# SH7_-_CAN.net
KiCad netlist of a schematic drawn in Altium Designer
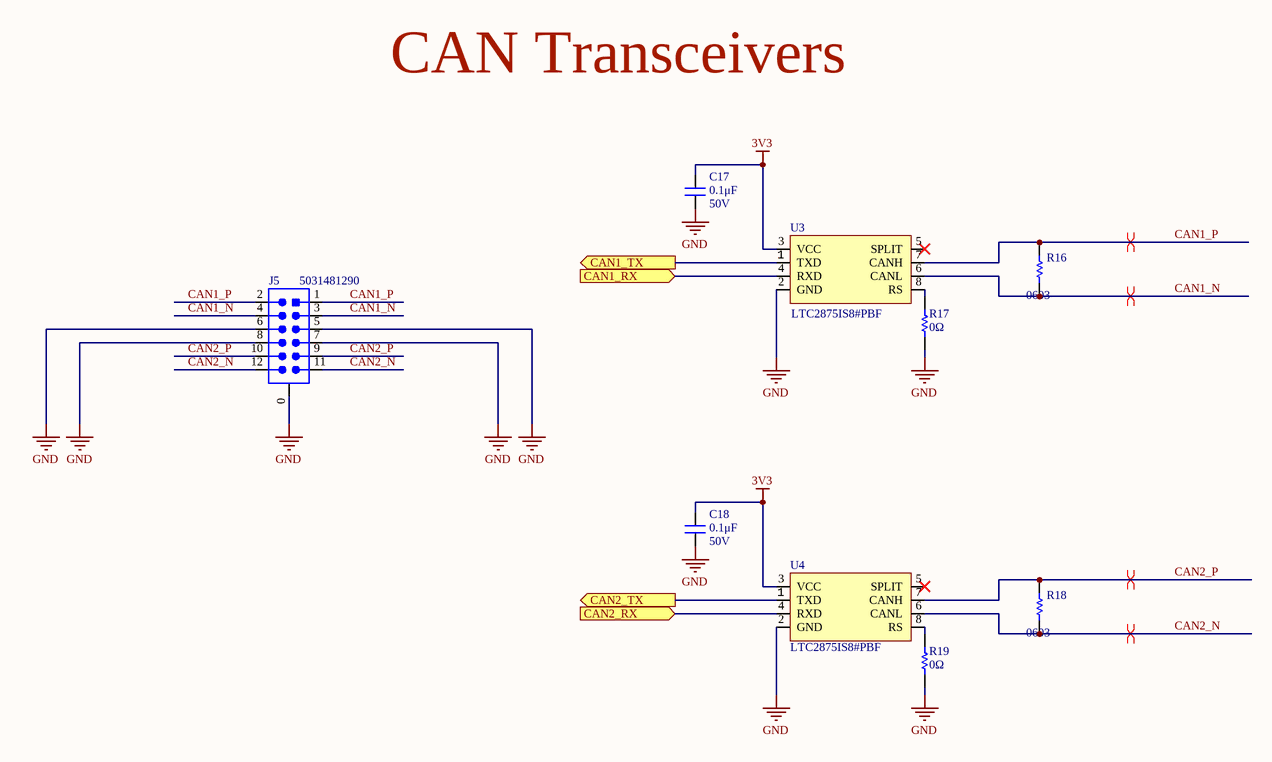
[diagram p0: SH7 - CAN.SchDoc]

(export (version "E")
  (design (tool "Eeschema 10.0.6"))
  (components
    (comp (ref "C17")
      (value "0.1μF")
      (footprint "CAP0603")
      (description "CAP CER 0.1UF 50V X7R 0603")
      (fields (field (name "VOLTAGE RATING") "50V") (field (name "Comment") "CAP_0.1uF_50V_0603"))
      (libsource (lib "UWRT_Schematic_Library_2020") (part "CAP_0.1uF_50V_0603"))
    )
    (comp (ref "C18")
      (value "0.1μF")
      (footprint "CAP0603")
      (description "CAP CER 0.1UF 50V X7R 0603")
      (fields (field (name "VOLTAGE RATING") "50V") (field (name "Comment") "CAP_0.1uF_50V_0603"))
      (libsource (lib "UWRT_Schematic_Library_2020") (part "CAP_0.1uF_50V_0603"))
    )
    (comp (ref "J5")
      (value "CON_6x2M_SM_RA")
      (footprint "MOLEX-5031481290")
      (description "CONN HEADER SMD RIGHT ANGLE 1.5MM PITCH")
      (fields (field (name "MANUFACTURER PART NUMBER 1") "5031481290"))
      (libsource (lib "UWRT_Schematic_Library_2020") (part "CON_6x2M_SM_RA"))
    )
    (comp (ref "R16")
      (value "RES_120Ω_0603_5%_HP")
      (footprint "RESC0603")
      (description "RES 120 OHM 5% 1/4W 0603")
      (fields (field (name "PACKAGE/FOOTPRINT") "0603"))
      (libsource (lib "UWRT_Schematic_Library_2020") (part "RES_120Ω_0603_5%_HP"))
    )
    (comp (ref "R17")
      (value "0Ω")
      (footprint "RESC0603")
      (description "RES 0 OHM JUMPER 1/10W 0603")
      (fields (field (name "Comment") "RES_0Ω_0603"))
      (libsource (lib "UWRT_Schematic_Library_2020") (part "RES_0Ω_0603"))
    )
    (comp (ref "R18")
      (value "RES_120Ω_0603_5%_HP")
      (footprint "RESC0603")
      (description "RES 120 OHM 5% 1/4W 0603")
      (fields (field (name "PACKAGE/FOOTPRINT") "0603"))
      (libsource (lib "UWRT_Schematic_Library_2020") (part "RES_120Ω_0603_5%_HP"))
    )
    (comp (ref "R19")
      (value "0Ω")
      (footprint "RESC0603")
      (description "RES 0 OHM JUMPER 1/10W 0603")
      (fields (field (name "Comment") "RES_0Ω_0603"))
      (libsource (lib "UWRT_Schematic_Library_2020") (part "RES_0Ω_0603"))
    )
    (comp (ref "U3")
      (value "LTC2875")
      (footprint "LT-S8_N")
      (description "IC TXRX CAN 4MBPS 8SO")
      (fields
        (field (name "MANUFACTURER PART NUMBER 1") "LTC2875IS8#PBF")
        (field (name "LCSC PART #") "C117076")
      )
      (libsource (lib "UWRT_Schematic_Library_2020") (part "LTC2875"))
    )
    (comp (ref "U4")
      (value "LTC2875")
      (footprint "LT-S8_N")
      (description "IC TXRX CAN 4MBPS 8SO")
      (fields
        (field (name "MANUFACTURER PART NUMBER 1") "LTC2875IS8#PBF")
        (field (name "LCSC PART #") "C117076")
      )
      (libsource (lib "UWRT_Schematic_Library_2020") (part "LTC2875"))
    )
  )
  (nets
    (net (code "1") (name "/CAN1_N") (class "Default")
      (node (ref "J5") (pin "3") (pinfunction "3_3") (pintype "passive"))
      (node (ref "J5") (pin "4") (pinfunction "4_4") (pintype "passive"))
      (node (ref "R16") (pin "1") (pinfunction "1_1") (pintype "passive"))
      (node (ref "U3") (pin "6") (pinfunction "CANL_6") (pintype "passive"))
    )
    (net (code "2") (name "/CAN1_P") (class "Default")
      (node (ref "J5") (pin "1") (pinfunction "1_1") (pintype "passive"))
      (node (ref "J5") (pin "2") (pinfunction "2_2") (pintype "passive"))
      (node (ref "R16") (pin "2") (pinfunction "2_2") (pintype "passive"))
      (node (ref "U3") (pin "7") (pinfunction "CANH_7") (pintype "passive"))
    )
    (net (code "3") (name "/CAN1_RX") (class "Default")
      (node (ref "U3") (pin "4") (pinfunction "RXD_4") (pintype "passive"))
    )
    (net (code "4") (name "/CAN1_TX") (class "Default")
      (node (ref "U3") (pin "1") (pinfunction "TXD_1") (pintype "passive"))
    )
    (net (code "5") (name "/CAN2_N") (class "Default")
      (node (ref "J5") (pin "11") (pinfunction "11_11") (pintype "passive"))
      (node (ref "J5") (pin "12") (pinfunction "12_12") (pintype "passive"))
      (node (ref "R18") (pin "1") (pinfunction "1_1") (pintype "passive"))
      (node (ref "U4") (pin "6") (pinfunction "CANL_6") (pintype "passive"))
    )
    (net (code "6") (name "/CAN2_P") (class "Default")
      (node (ref "J5") (pin "10") (pinfunction "10_10") (pintype "passive"))
      (node (ref "J5") (pin "9") (pinfunction "9_9") (pintype "passive"))
      (node (ref "R18") (pin "2") (pinfunction "2_2") (pintype "passive"))
      (node (ref "U4") (pin "7") (pinfunction "CANH_7") (pintype "passive"))
    )
    (net (code "7") (name "/CAN2_RX") (class "Default")
      (node (ref "U4") (pin "4") (pinfunction "RXD_4") (pintype "passive"))
    )
    (net (code "8") (name "/CAN2_TX") (class "Default")
      (node (ref "U4") (pin "1") (pinfunction "TXD_1") (pintype "passive"))
    )
    (net (code "9") (name "3V3") (class "Default")
      (node (ref "C17") (pin "1") (pinfunction "1_1") (pintype "passive"))
      (node (ref "C18") (pin "1") (pinfunction "1_1") (pintype "passive"))
      (node (ref "U3") (pin "3") (pinfunction "VCC_3") (pintype "passive"))
      (node (ref "U4") (pin "3") (pinfunction "VCC_3") (pintype "passive"))
    )
    (net (code "10") (name "GND") (class "Default")
      (node (ref "C17") (pin "2") (pinfunction "2_2") (pintype "passive"))
      (node (ref "C18") (pin "2") (pinfunction "2_2") (pintype "passive"))
      (node (ref "J5") (pin "0") (pinfunction "0_0") (pintype "passive"))
      (node (ref "J5") (pin "5") (pinfunction "5_5") (pintype "passive"))
      (node (ref "J5") (pin "6") (pinfunction "6_6") (pintype "passive"))
      (node (ref "J5") (pin "7") (pinfunction "7_7") (pintype "passive"))
      (node (ref "J5") (pin "8") (pinfunction "8_8") (pintype "passive"))
      (node (ref "R17") (pin "1") (pinfunction "1_1") (pintype "passive"))
      (node (ref "R19") (pin "1") (pinfunction "1_1") (pintype "passive"))
      (node (ref "U3") (pin "2") (pinfunction "GND_2") (pintype "passive"))
      (node (ref "U4") (pin "2") (pinfunction "GND_2") (pintype "passive"))
    )
    (net (code "11") (name "Net-(U3-RS)") (class "Default")
      (node (ref "R17") (pin "2") (pinfunction "2_2") (pintype "passive"))
      (node (ref "U3") (pin "8") (pinfunction "RS_8") (pintype "passive"))
    )
    (net (code "12") (name "Net-(U4-RS)") (class "Default")
      (node (ref "R19") (pin "2") (pinfunction "2_2") (pintype "passive"))
      (node (ref "U4") (pin "8") (pinfunction "RS_8") (pintype "passive"))
    )
    (net (code "13") (name "unconnected-(U3-SPLIT-Pad5)") (class "Default")
      (node (ref "U3") (pin "5") (pinfunction "SPLIT_5") (pintype "passive+no_connect"))
    )
    (net (code "14") (name "unconnected-(U4-SPLIT-Pad5)") (class "Default")
      (node (ref "U4") (pin "5") (pinfunction "SPLIT_5") (pintype "passive+no_connect"))
    )
  )
)
